# powerblade_3v5.net
KiCad netlist of a schematic drawn in EAGLE
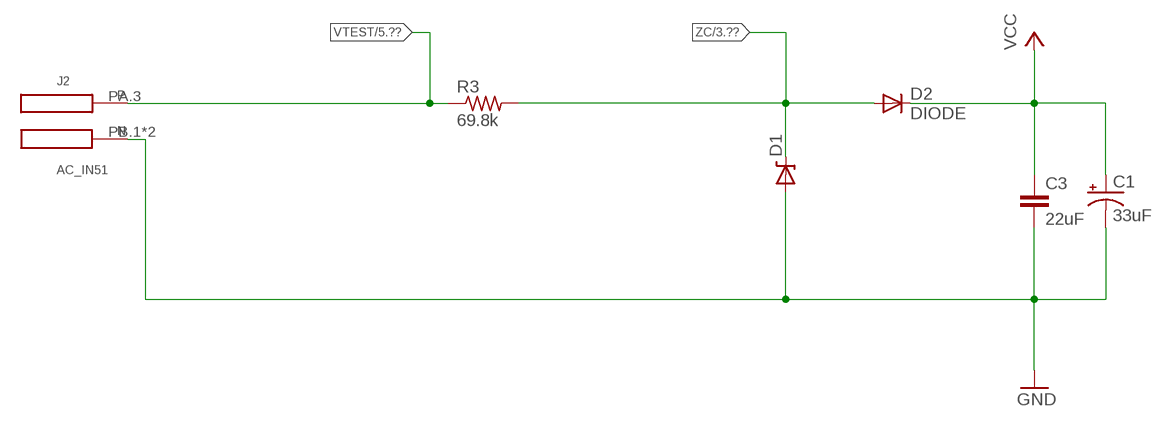
[diagram p0: schematic, sheet 1]
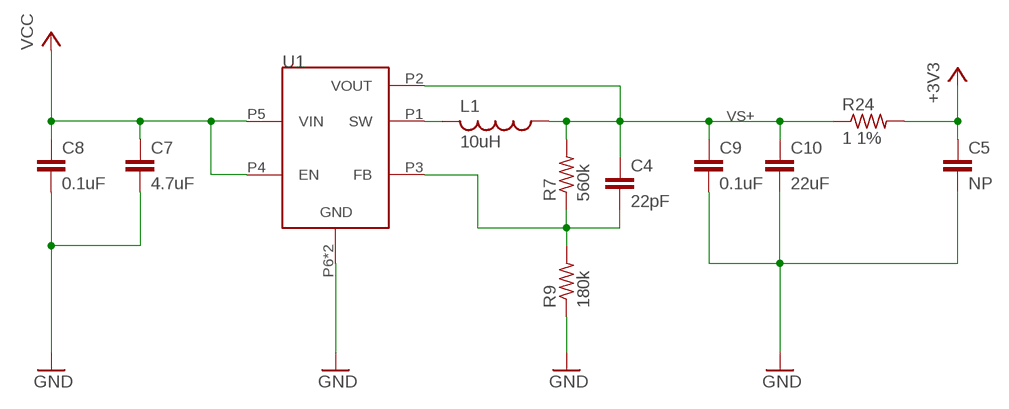
[diagram p1: schematic, sheet 2]
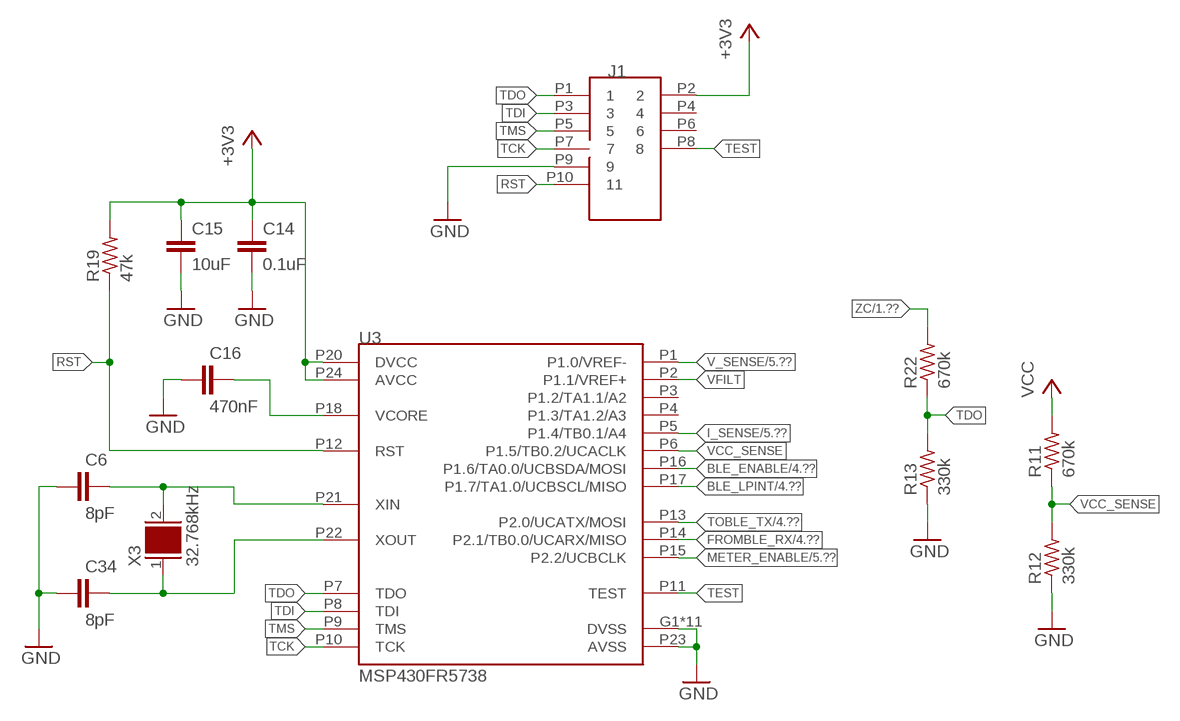
[diagram p2: schematic, sheet 3]
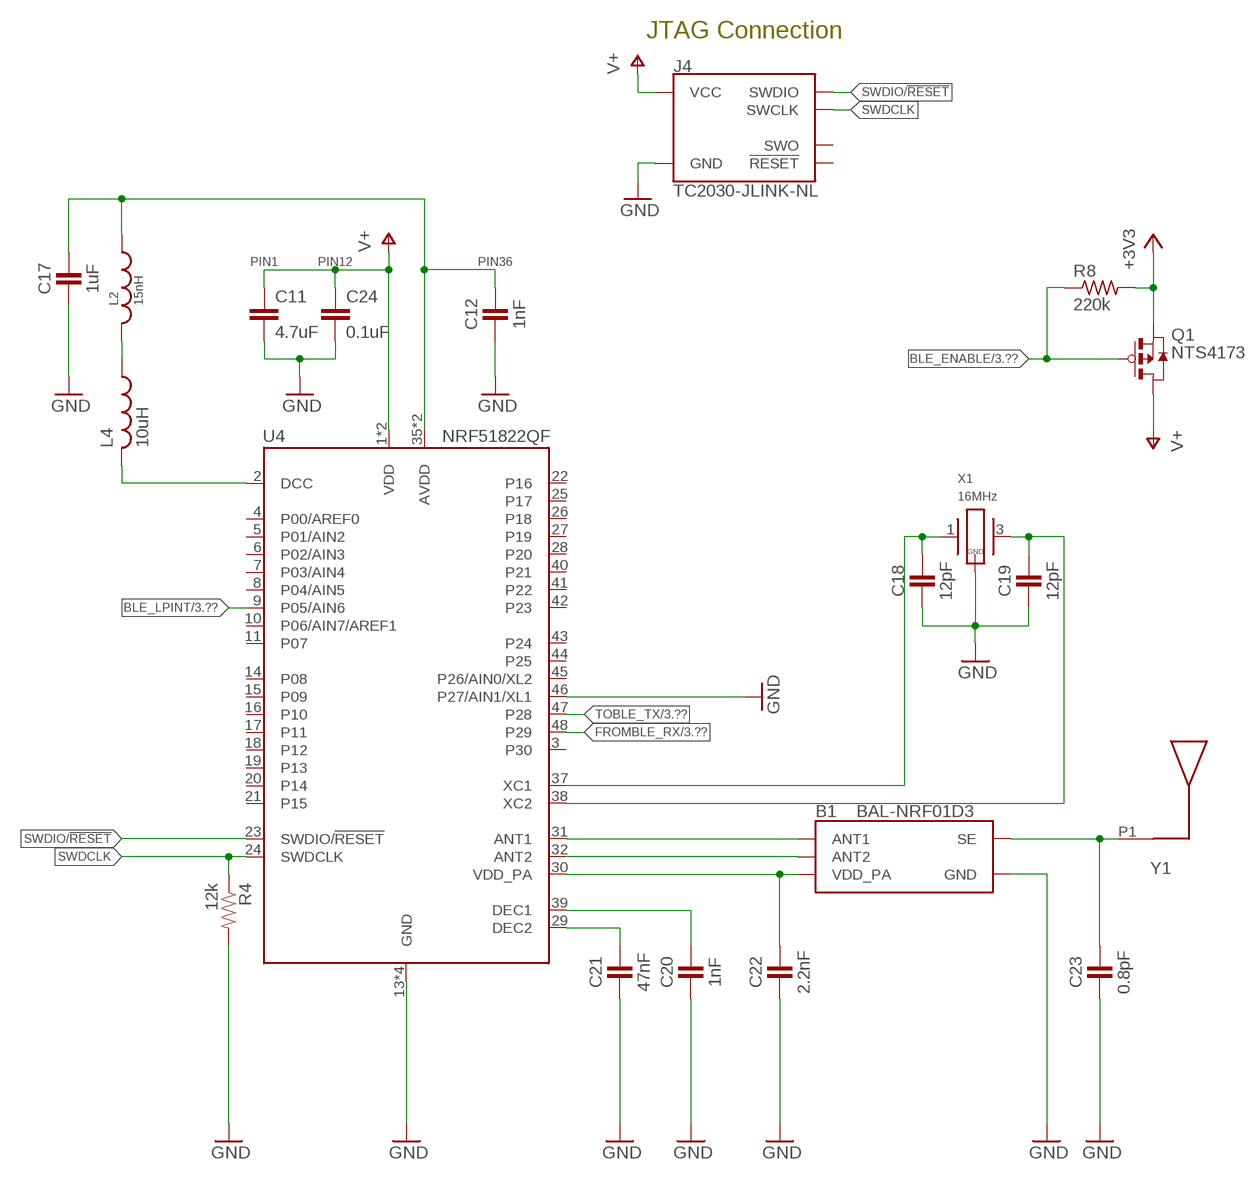
[diagram p3: schematic, sheet 4]
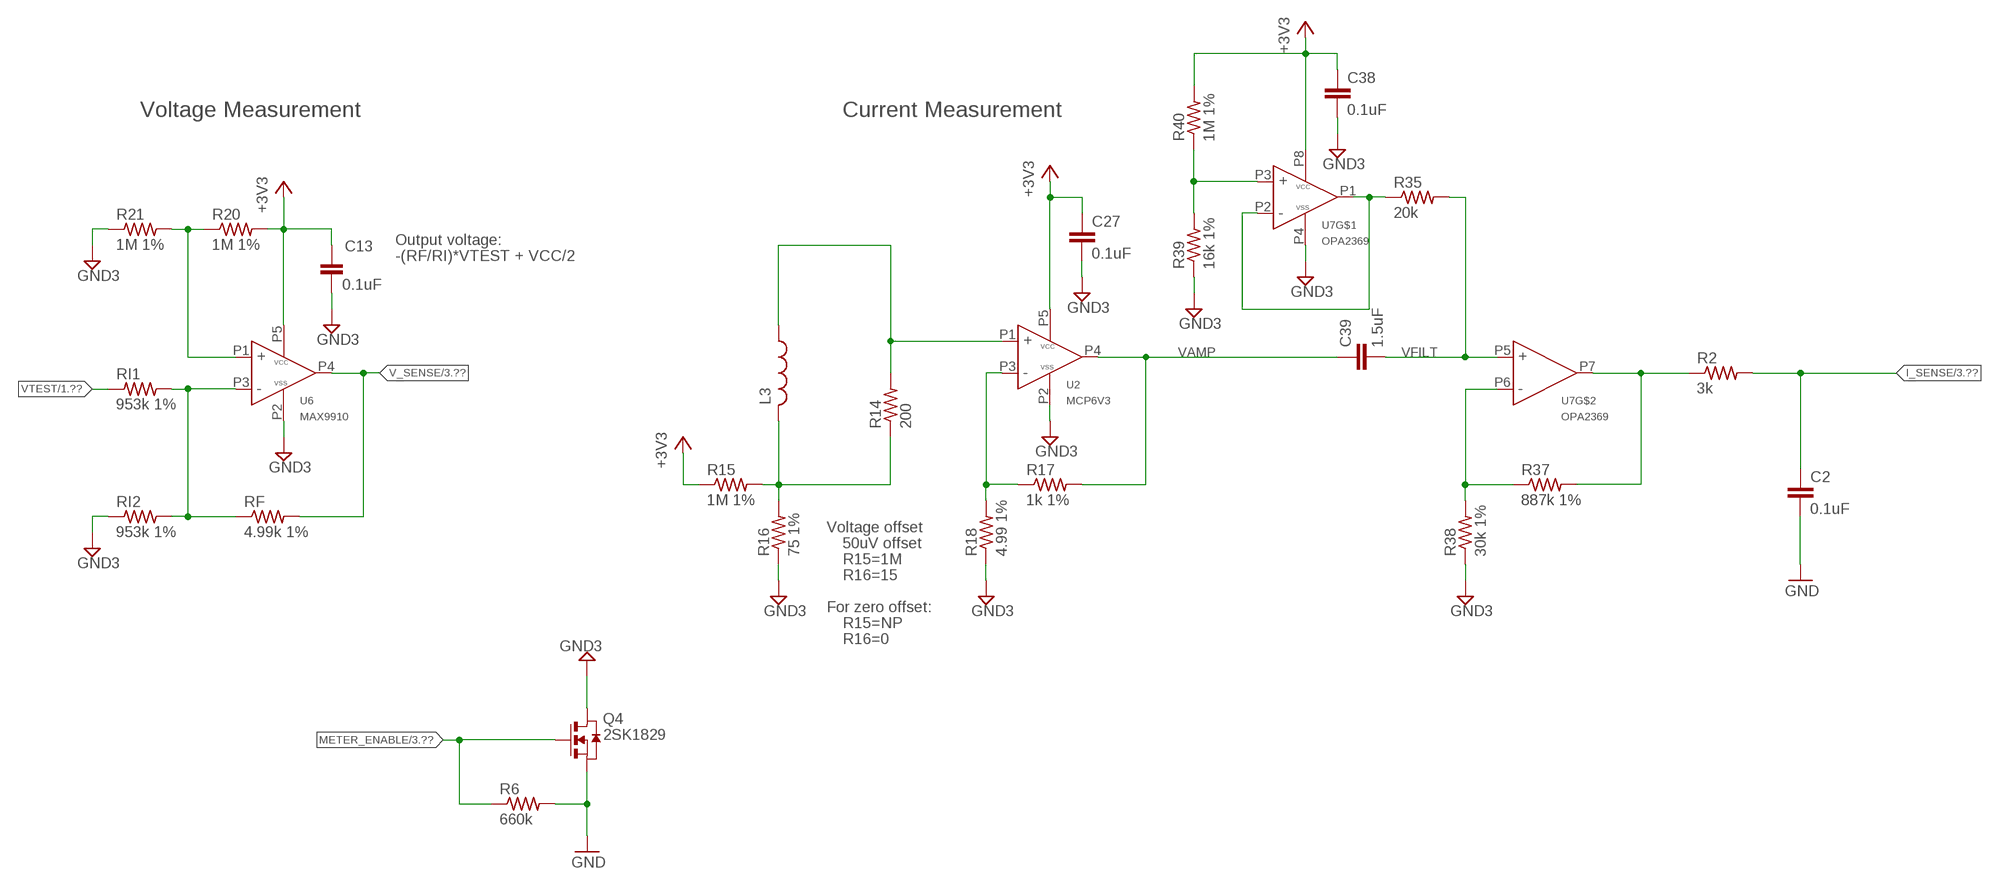
[diagram p4: schematic, sheet 5]

(export (version "E")
  (design (tool "Eeschema 10.0.6"))
  (components
    (comp (ref "B1")
      (value "BAL-NRF01D3")
      (footprint "eagle-import:BAL-NRF01D3")
      (libsource (lib "eagle-import") (part "BAL-NRF01D3"))
    )
    (comp (ref "C11")
      (value "4.7uF")
      (footprint "eagle-import:C0402")
      (libsource (lib "eagle-import") (part "C-EUC0402"))
    )
    (comp (ref "C12")
      (value "1nF")
      (footprint "eagle-import:0402_CAP")
      (libsource (lib "eagle-import") (part "CAPACITOR"))
    )
    (comp (ref "C17")
      (value "1uF")
      (footprint "eagle-import:0402_CAP")
      (libsource (lib "eagle-import") (part "CAPACITOR"))
    )
    (comp (ref "C18")
      (value "12pF")
      (footprint "eagle-import:0402_CAP")
      (libsource (lib "eagle-import") (part "CAPACITOR"))
    )
    (comp (ref "C19")
      (value "12pF")
      (footprint "eagle-import:0402_CAP")
      (libsource (lib "eagle-import") (part "CAPACITOR"))
    )
    (comp (ref "C20")
      (value "1nF")
      (footprint "eagle-import:0402_CAP")
      (libsource (lib "eagle-import") (part "CAPACITOR"))
    )
    (comp (ref "C21")
      (value "47nF")
      (footprint "eagle-import:0402_CAP")
      (libsource (lib "eagle-import") (part "CAPACITOR"))
    )
    (comp (ref "C22")
      (value "2.2nF")
      (footprint "eagle-import:0402_CAP")
      (libsource (lib "eagle-import") (part "CAPACITOR"))
    )
    (comp (ref "C23")
      (value "0.8pF")
      (footprint "eagle-import:0402_CAP")
      (libsource (lib "eagle-import") (part "CAPACITOR"))
    )
    (comp (ref "C24")
      (value "0.1uF")
      (footprint "eagle-import:C0402")
      (libsource (lib "eagle-import") (part "C-EUC0402"))
    )
    (comp (ref "J4")
      (value "TC2030-JLINK-NL")
      (footprint "eagle-import:TC2030-IDC-NL")
      (libsource (lib "eagle-import") (part "TC2030-JLINK-NL"))
    )
    (comp (ref "L2")
      (value "15nH")
      (footprint "eagle-import:0402_CAP")
      (libsource (lib "eagle-import") (part "INDUCTOR0402"))
    )
    (comp (ref "L4")
      (value "10uH")
      (footprint "eagle-import:C0603_TN")
      (libsource (lib "eagle-import") (part "L-USL0603_TN"))
    )
    (comp (ref "Q1")
      (value "NTS4173")
      (footprint "eagle-import:SC-70-3")
      (libsource (lib "eagle-import") (part "NTS4173"))
    )
    (comp (ref "R4")
      (value "12k")
      (footprint "eagle-import:0402_RES")
      (libsource (lib "eagle-import") (part "RESISTOR"))
    )
    (comp (ref "R8")
      (value "220k")
      (footprint "eagle-import:R0402_SM")
      (libsource (lib "eagle-import") (part "R-US_R0402_SM"))
    )
    (comp (ref "U4")
      (value "NRF51822QF")
      (footprint "eagle-import:QFN-48-6MM")
      (libsource (lib "eagle-import") (part "NRF51822QF"))
    )
    (comp (ref "X1")
      (value "16MHz")
      (footprint "eagle-import:TXC-8Y")
      (libsource (lib "eagle-import") (part "TXC-8Y"))
    )
    (comp (ref "Y1")
      (value "UREACH_XTEND")
      (footprint "eagle-import:UREACH_XTEND")
      (libsource (lib "eagle-import") (part "UREACH_XTEND"))
    )
    (comp (ref "C2")
      (value "0.1uF")
      (footprint "eagle-import:C0402")
      (libsource (lib "eagle-import") (part "C-EUC0402"))
    )
    (comp (ref "C13")
      (value "0.1uF")
      (footprint "eagle-import:0402_CAP")
      (libsource (lib "eagle-import") (part "CAPACITOR"))
    )
    (comp (ref "C27")
      (value "0.1uF")
      (footprint "eagle-import:C0402")
      (libsource (lib "eagle-import") (part "C-EUC0402"))
    )
    (comp (ref "C38")
      (value "0.1uF")
      (footprint "eagle-import:C0402")
      (libsource (lib "eagle-import") (part "C-EUC0402"))
    )
    (comp (ref "C39")
      (value "1.5uF")
      (footprint "eagle-import:C0402")
      (libsource (lib "eagle-import") (part "C-EUC0402"))
    )
    (comp (ref "L3")
      (value "L-USL0805")
      (footprint "eagle-import:L0805")
      (libsource (lib "eagle-import") (part "L-USL0805"))
    )
    (comp (ref "Q4")
      (value "2SK1829")
      (footprint "eagle-import:SC-70-3")
      (libsource (lib "eagle-import") (part "2SK1829"))
    )
    (comp (ref "R2")
      (value "3k")
      (footprint "eagle-import:R0402_SM")
      (libsource (lib "eagle-import") (part "R-US_R0402_SM"))
    )
    (comp (ref "R6")
      (value "660k")
      (footprint "eagle-import:R0402")
      (libsource (lib "eagle-import") (part "R-US_R0402"))
    )
    (comp (ref "R14")
      (value "200")
      (footprint "eagle-import:R0402")
      (libsource (lib "eagle-import") (part "R-US_R0402"))
    )
    (comp (ref "R15")
      (value "1M 1%")
      (footprint "eagle-import:R0402")
      (libsource (lib "eagle-import") (part "R-US_R0402"))
    )
    (comp (ref "R16")
      (value "75 1%")
      (footprint "eagle-import:R0402")
      (libsource (lib "eagle-import") (part "R-US_R0402"))
    )
    (comp (ref "R17")
      (value "1k 1%")
      (footprint "eagle-import:R0402")
      (libsource (lib "eagle-import") (part "R-US_R0402"))
    )
    (comp (ref "R18")
      (value "4.99 1%")
      (footprint "eagle-import:R0402")
      (libsource (lib "eagle-import") (part "R-US_R0402"))
    )
    (comp (ref "R20")
      (value "1M 1%")
      (footprint "eagle-import:R0402")
      (libsource (lib "eagle-import") (part "R-US_R0402"))
    )
    (comp (ref "R21")
      (value "1M 1%")
      (footprint "eagle-import:R0402_SM")
      (libsource (lib "eagle-import") (part "R-US_R0402_SM"))
    )
    (comp (ref "R35")
      (value "20k")
      (footprint "eagle-import:R0402")
      (libsource (lib "eagle-import") (part "R-US_R0402"))
    )
    (comp (ref "R37")
      (value "887k 1%")
      (footprint "eagle-import:R0402")
      (libsource (lib "eagle-import") (part "R-US_R0402"))
    )
    (comp (ref "R38")
      (value "30k 1%")
      (footprint "eagle-import:R0402")
      (libsource (lib "eagle-import") (part "R-US_R0402"))
    )
    (comp (ref "R39")
      (value "16k 1%")
      (footprint "eagle-import:R0402")
      (libsource (lib "eagle-import") (part "R-US_R0402"))
    )
    (comp (ref "R40")
      (value "1M 1%")
      (footprint "eagle-import:R0402")
      (libsource (lib "eagle-import") (part "R-US_R0402"))
    )
    (comp (ref "RF")
      (value "4.99k 1%")
      (footprint "eagle-import:R0402")
      (libsource (lib "eagle-import") (part "R-US_R0402"))
    )
    (comp (ref "RI1")
      (value "953k 1%")
      (footprint "eagle-import:R0402")
      (libsource (lib "eagle-import") (part "R-US_R0402"))
    )
    (comp (ref "RI2")
      (value "953k 1%")
      (footprint "eagle-import:R0402")
      (libsource (lib "eagle-import") (part "R-US_R0402"))
    )
    (comp (ref "U2")
      (value "MCP6V3")
      (footprint "eagle-import:SC70-5")
      (fields (field (name "DIGIKEY") "296-19547-1-ND"))
      (libsource (lib "eagle-import") (part "MCP6V3"))
    )
    (comp (ref "U6")
      (value "MAX9910")
      (footprint "eagle-import:SC70-5")
      (fields (field (name "DIGIKEY") "296-25252-1-ND"))
      (libsource (lib "eagle-import") (part "MAX9910"))
    )
    (comp (ref "U7")
      (value "OPA2369")
      (footprint "eagle-import:SOT-23-8")
      (libsource (lib "eagle-import") (part "OPA2369"))
    )
    (comp (ref "C6")
      (value "8pF")
      (footprint "eagle-import:C0402")
      (libsource (lib "eagle-import") (part "C-EUC0402"))
    )
    (comp (ref "C14")
      (value "0.1uF")
      (footprint "eagle-import:C0402")
      (libsource (lib "eagle-import") (part "C-EUC0402"))
    )
    (comp (ref "C15")
      (value "10uF")
      (footprint "eagle-import:C0603_SM")
      (libsource (lib "eagle-import") (part "C-EUC0603_SM"))
    )
    (comp (ref "C16")
      (value "470nF")
      (footprint "eagle-import:C0402")
      (libsource (lib "eagle-import") (part "C-EUC0402"))
    )
    (comp (ref "C34")
      (value "8pF")
      (footprint "eagle-import:C0402")
      (libsource (lib "eagle-import") (part "C-EUC0402"))
    )
    (comp (ref "J1")
      (value "JTAG_14PIN_IDC-ND")
      (footprint "eagle-import:TC2050-IDC-NL-430-ND")
      (libsource (lib "eagle-import") (part "JTAG_14PIN_IDC-ND"))
    )
    (comp (ref "R11")
      (value "670k")
      (footprint "eagle-import:R0402")
      (libsource (lib "eagle-import") (part "R-US_R0402"))
    )
    (comp (ref "R12")
      (value "330k")
      (footprint "eagle-import:R0402")
      (libsource (lib "eagle-import") (part "R-US_R0402"))
    )
    (comp (ref "R13")
      (value "330k")
      (footprint "eagle-import:R0402")
      (libsource (lib "eagle-import") (part "R-US_R0402"))
    )
    (comp (ref "R19")
      (value "47k")
      (footprint "eagle-import:R0402")
      (libsource (lib "eagle-import") (part "R-US_R0402"))
    )
    (comp (ref "R22")
      (value "670k")
      (footprint "eagle-import:R0402")
      (libsource (lib "eagle-import") (part "R-US_R0402"))
    )
    (comp (ref "U3")
      (value "MSP430FR5738")
      (footprint "eagle-import:VQFN-24")
      (libsource (lib "eagle-import") (part "MSP430FR5738"))
    )
    (comp (ref "X3")
      (value "32.768kHz")
      (footprint "eagle-import:0805")
      (libsource (lib "eagle-import") (part "CRYSTAL_0805"))
    )
    (comp (ref "C1")
      (value "33uF")
      (footprint "eagle-import:CPOL0805_SM")
      (libsource (lib "eagle-import") (part "CPOL-US0805_SM"))
    )
    (comp (ref "C3")
      (value "22uF")
      (footprint "eagle-import:C0603_SM")
      (libsource (lib "eagle-import") (part "C-EUC0603_SM"))
    )
    (comp (ref "D1")
      (value "ZENERBZT52")
      (footprint "eagle-import:BZT52")
      (fields (field (name "DIGIKEY") "BZT52C10T-7DICT-ND "))
      (libsource (lib "eagle-import") (part "ZENERBZT52"))
    )
    (comp (ref "D2")
      (value "DIODE")
      (footprint "eagle-import:BAS521")
      (libsource (lib "eagle-import") (part "DIODE"))
    )
    (comp (ref "J2")
      (value "AC_IN51")
      (footprint "eagle-import:AC3_51")
      (libsource (lib "eagle-import") (part "AC_IN51"))
    )
    (comp (ref "R3")
      (value "69.8k")
      (footprint "eagle-import:R1210")
      (libsource (lib "eagle-import") (part "R-US_R1210"))
    )
    (comp (ref "C4")
      (value "22pF")
      (footprint "eagle-import:C0402")
      (libsource (lib "eagle-import") (part "C-EUC0402"))
    )
    (comp (ref "C5")
      (value "NP")
      (footprint "eagle-import:C0603_TN")
      (libsource (lib "eagle-import") (part "C-EUC0603_TN"))
    )
    (comp (ref "C7")
      (value "4.7uF")
      (footprint "eagle-import:C0402")
      (libsource (lib "eagle-import") (part "C-EUC0402"))
    )
    (comp (ref "C8")
      (value "0.1uF")
      (footprint "eagle-import:C0402")
      (libsource (lib "eagle-import") (part "C-EUC0402"))
    )
    (comp (ref "C9")
      (value "0.1uF")
      (footprint "eagle-import:C0402_SM")
      (libsource (lib "eagle-import") (part "C-EUC0402_SM"))
    )
    (comp (ref "C10")
      (value "22uF")
      (footprint "eagle-import:C0603_SM")
      (libsource (lib "eagle-import") (part "C-EUC0603_SM"))
    )
    (comp (ref "L1")
      (value "10uH")
      (footprint "eagle-import:L0805")
      (libsource (lib "eagle-import") (part "L-USL0805"))
    )
    (comp (ref "R7")
      (value "560k")
      (footprint "eagle-import:R0402")
      (libsource (lib "eagle-import") (part "R-US_R0402"))
    )
    (comp (ref "R9")
      (value "180k")
      (footprint "eagle-import:R0402")
      (libsource (lib "eagle-import") (part "R-US_R0402"))
    )
    (comp (ref "R24")
      (value "1 1%")
      (footprint "eagle-import:R0603_SM")
      (libsource (lib "eagle-import") (part "R-US_R0603_SM"))
    )
    (comp (ref "U1")
      (value "TPS62122")
      (footprint "eagle-import:WDFN-6")
      (libsource (lib "eagle-import") (part "TPS62122"))
    )
  )
  (nets
    (net (code "1") (name "+3V3") (class "Default")
      (node (ref "C13") (pin "1") (pinfunction "1_1") (pintype "bidirectional"))
      (node (ref "C14") (pin "1") (pinfunction "1_1") (pintype "passive"))
      (node (ref "C15") (pin "1") (pinfunction "1_1") (pintype "passive"))
      (node (ref "C27") (pin "1") (pinfunction "1_1") (pintype "passive"))
      (node (ref "C38") (pin "1") (pinfunction "1_1") (pintype "passive"))
      (node (ref "C5") (pin "1") (pinfunction "1_1") (pintype "passive"))
      (node (ref "J1") (pin "P2") (pinfunction "2_P2") (pintype "bidirectional"))
      (node (ref "Q1") (pin "P2") (pinfunction "S_P2") (pintype "passive"))
      (node (ref "R15") (pin "1") (pinfunction "1_1") (pintype "passive"))
      (node (ref "R19") (pin "2") (pinfunction "2_2") (pintype "passive"))
      (node (ref "R20") (pin "2") (pinfunction "2_2") (pintype "passive"))
      (node (ref "R24") (pin "2") (pinfunction "2_2") (pintype "passive"))
      (node (ref "R40") (pin "2") (pinfunction "2_2") (pintype "passive"))
      (node (ref "R8") (pin "2") (pinfunction "2_2") (pintype "passive"))
      (node (ref "U2") (pin "P5") (pinfunction "VCC_P5") (pintype "bidirectional"))
      (node (ref "U3") (pin "P20") (pinfunction "DVCC_P20") (pintype "bidirectional"))
      (node (ref "U3") (pin "P24") (pinfunction "AVCC_P24") (pintype "bidirectional"))
      (node (ref "U6") (pin "P5") (pinfunction "VCC_P5") (pintype "bidirectional"))
      (node (ref "U7") (pin "P8") (pinfunction "VCC_P8") (pintype "bidirectional"))
    )
    (net (code "2") (name "BLE_ENABLE") (class "Default")
      (node (ref "Q1") (pin "P1") (pinfunction "G_P1") (pintype "passive"))
      (node (ref "R8") (pin "1") (pinfunction "1_1") (pintype "passive"))
      (node (ref "U3") (pin "P16") (pinfunction "P1.6/TA0.0/UCBSDA/MOSI_P16") (pintype "bidirectional"))
    )
    (net (code "3") (name "BLE_LPINT") (class "Default")
      (node (ref "U3") (pin "P17") (pinfunction "P1.7/TA1.0/UCBSCL/MISO_P17") (pintype "bidirectional"))
      (node (ref "U4") (pin "9") (pinfunction "P05/AIN6_9") (pintype "bidirectional"))
    )
    (net (code "4") (name "FROMBLE_RX") (class "Default")
      (node (ref "U3") (pin "P14") (pinfunction "P2.1/TB0.0/UCARX/MISO_P14") (pintype "bidirectional"))
      (node (ref "U4") (pin "48") (pinfunction "P29_48") (pintype "bidirectional"))
    )
    (net (code "5") (name "GND") (class "Default")
      (node (ref "B1") (pin "GND") (pinfunction "GND_GND") (pintype "bidirectional"))
      (node (ref "C1") (pin "-") (pinfunction "-_-") (pintype "passive"))
      (node (ref "C10") (pin "2") (pinfunction "2_2") (pintype "passive"))
      (node (ref "C11") (pin "2") (pinfunction "2_2") (pintype "passive"))
      (node (ref "C12") (pin "2") (pinfunction "2_2") (pintype "bidirectional"))
      (node (ref "C14") (pin "2") (pinfunction "2_2") (pintype "passive"))
      (node (ref "C15") (pin "2") (pinfunction "2_2") (pintype "passive"))
      (node (ref "C16") (pin "1") (pinfunction "1_1") (pintype "passive"))
      (node (ref "C17") (pin "2") (pinfunction "2_2") (pintype "bidirectional"))
      (node (ref "C18") (pin "2") (pinfunction "2_2") (pintype "bidirectional"))
      (node (ref "C19") (pin "2") (pinfunction "2_2") (pintype "bidirectional"))
      (node (ref "C2") (pin "2") (pinfunction "2_2") (pintype "passive"))
      (node (ref "C20") (pin "2") (pinfunction "2_2") (pintype "bidirectional"))
      (node (ref "C21") (pin "2") (pinfunction "2_2") (pintype "bidirectional"))
      (node (ref "C22") (pin "2") (pinfunction "2_2") (pintype "bidirectional"))
      (node (ref "C23") (pin "2") (pinfunction "2_2") (pintype "bidirectional"))
      (node (ref "C24") (pin "2") (pinfunction "2_2") (pintype "passive"))
      (node (ref "C3") (pin "2") (pinfunction "2_2") (pintype "passive"))
      (node (ref "C34") (pin "1") (pinfunction "1_1") (pintype "passive"))
      (node (ref "C5") (pin "2") (pinfunction "2_2") (pintype "passive"))
      (node (ref "C6") (pin "1") (pinfunction "1_1") (pintype "passive"))
      (node (ref "C7") (pin "2") (pinfunction "2_2") (pintype "passive"))
      (node (ref "C8") (pin "2") (pinfunction "2_2") (pintype "passive"))
      (node (ref "C9") (pin "2") (pinfunction "2_2") (pintype "passive"))
      (node (ref "D1") (pin "A") (pinfunction "A_A") (pintype "passive"))
      (node (ref "J1") (pin "P9") (pinfunction "9_P9") (pintype "bidirectional"))
      (node (ref "J2") (pin "PB.1") (pinfunction "N_PB.1") (pintype "bidirectional"))
      (node (ref "J2") (pin "PB.3") (pinfunction "N_PB.3") (pintype "bidirectional"))
      (node (ref "J4") (pin "5") (pinfunction "GND_5") (pintype "bidirectional"))
      (node (ref "Q4") (pin "P2") (pinfunction "S_P2") (pintype "passive"))
      (node (ref "R12") (pin "1") (pinfunction "1_1") (pintype "passive"))
      (node (ref "R13") (pin "1") (pinfunction "1_1") (pintype "passive"))
      (node (ref "R4") (pin "2") (pinfunction "2_2") (pintype "passive"))
      (node (ref "R6") (pin "2") (pinfunction "2_2") (pintype "passive"))
      (node (ref "R9") (pin "1") (pinfunction "1_1") (pintype "passive"))
      (node (ref "U1") (pin "P6") (pinfunction "GND_P6") (pintype "bidirectional"))
      (node (ref "U1") (pin "PAD") (pinfunction "GND_PAD") (pintype "bidirectional"))
      (node (ref "U3") (pin "G1") (pinfunction "DVSS_G1") (pintype "bidirectional"))
      (node (ref "U3") (pin "G2") (pinfunction "DVSS_G2") (pintype "bidirectional"))
      (node (ref "U3") (pin "G3") (pinfunction "DVSS_G3") (pintype "bidirectional"))
      (node (ref "U3") (pin "G4") (pinfunction "DVSS_G4") (pintype "bidirectional"))
      (node (ref "U3") (pin "G5") (pinfunction "DVSS_G5") (pintype "bidirectional"))
      (node (ref "U3") (pin "G6") (pinfunction "DVSS_G6") (pintype "bidirectional"))
      (node (ref "U3") (pin "G7") (pinfunction "DVSS_G7") (pintype "bidirectional"))
      (node (ref "U3") (pin "G8") (pinfunction "DVSS_G8") (pintype "bidirectional"))
      (node (ref "U3") (pin "G9") (pinfunction "DVSS_G9") (pintype "bidirectional"))
      (node (ref "U3") (pin "P19") (pinfunction "DVSS_P19") (pintype "bidirectional"))
      (node (ref "U3") (pin "P23") (pinfunction "AVSS_P23") (pintype "bidirectional"))
      (node (ref "U3") (pin "PAD") (pinfunction "DVSS_PAD") (pintype "bidirectional"))
      (node (ref "U4") (pin "13") (pinfunction "GND_13") (pintype "bidirectional"))
      (node (ref "U4") (pin "33") (pinfunction "GND_33") (pintype "bidirectional"))
      (node (ref "U4") (pin "34") (pinfunction "GND_34") (pintype "bidirectional"))
      (node (ref "U4") (pin "46") (pinfunction "P27/AIN1/XL1_46") (pintype "bidirectional"))
      (node (ref "U4") (pin "GND") (pinfunction "GND_GND") (pintype "bidirectional"))
      (node (ref "X1") (pin "2") (pinfunction "GND_2") (pintype "bidirectional"))
      (node (ref "X1") (pin "4") (pinfunction "GND_4") (pintype "bidirectional"))
    )
    (net (code "6") (name "GND3") (class "Default")
      (node (ref "C13") (pin "2") (pinfunction "2_2") (pintype "bidirectional"))
      (node (ref "C27") (pin "2") (pinfunction "2_2") (pintype "passive"))
      (node (ref "C38") (pin "2") (pinfunction "2_2") (pintype "passive"))
      (node (ref "Q4") (pin "P3") (pinfunction "D_P3") (pintype "passive"))
      (node (ref "R16") (pin "1") (pinfunction "1_1") (pintype "passive"))
      (node (ref "R18") (pin "1") (pinfunction "1_1") (pintype "passive"))
      (node (ref "R21") (pin "1") (pinfunction "1_1") (pintype "passive"))
      (node (ref "R38") (pin "1") (pinfunction "1_1") (pintype "passive"))
      (node (ref "R39") (pin "1") (pinfunction "1_1") (pintype "passive"))
      (node (ref "RI2") (pin "1") (pinfunction "1_1") (pintype "passive"))
      (node (ref "U2") (pin "P2") (pinfunction "VSS_P2") (pintype "bidirectional"))
      (node (ref "U6") (pin "P2") (pinfunction "VSS_P2") (pintype "bidirectional"))
      (node (ref "U7") (pin "P4") (pinfunction "VSS_P4") (pintype "bidirectional"))
    )
    (net (code "7") (name "I_SENSE") (class "Default")
      (node (ref "C2") (pin "1") (pinfunction "1_1") (pintype "passive"))
      (node (ref "R2") (pin "2") (pinfunction "2_2") (pintype "passive"))
      (node (ref "U3") (pin "P5") (pinfunction "P1.4/TB0.1/A4_P5") (pintype "bidirectional"))
    )
    (net (code "8") (name "METER_ENABLE") (class "Default")
      (node (ref "Q4") (pin "P1") (pinfunction "G_P1") (pintype "passive"))
      (node (ref "R6") (pin "1") (pinfunction "1_1") (pintype "passive"))
      (node (ref "U3") (pin "P15") (pinfunction "P2.2/UCBCLK_P15") (pintype "bidirectional"))
    )
    (net (code "9") (name "Net-(B1-PadSE)") (class "Default")
      (node (ref "B1") (pin "SE") (pinfunction "SE_SE") (pintype "bidirectional"))
      (node (ref "C23") (pin "1") (pinfunction "1_1") (pintype "bidirectional"))
      (node (ref "Y1") (pin "P1") (pinfunction "P1_P1") (pintype "bidirectional"))
    )
    (net (code "10") (name "Net-(B1-VDD_PA)") (class "Default")
      (node (ref "B1") (pin "VCC") (pinfunction "VDD_PA_VCC") (pintype "bidirectional"))
      (node (ref "C22") (pin "1") (pinfunction "1_1") (pintype "bidirectional"))
      (node (ref "U4") (pin "30") (pinfunction "VDD_PA_30") (pintype "bidirectional"))
    )
    (net (code "11") (name "Net-(C12-Pad1)") (class "Default")
      (node (ref "C12") (pin "1") (pinfunction "1_1") (pintype "bidirectional"))
      (node (ref "C17") (pin "1") (pinfunction "1_1") (pintype "bidirectional"))
      (node (ref "L2") (pin "1") (pinfunction "1_1") (pintype "bidirectional"))
      (node (ref "U4") (pin "35") (pinfunction "AVDD_35") (pintype "bidirectional"))
      (node (ref "U4") (pin "36") (pinfunction "AVDD_36") (pintype "bidirectional"))
    )
    (net (code "12") (name "Net-(L2-Pad2)") (class "Default")
      (node (ref "L2") (pin "2") (pinfunction "2_2") (pintype "bidirectional"))
      (node (ref "L4") (pin "1") (pinfunction "1_1") (pintype "passive"))
    )
    (net (code "13") (name "Net-(L3-Pad2)") (class "Default")
      (node (ref "L3") (pin "2") (pinfunction "2_2") (pintype "passive"))
      (node (ref "R14") (pin "1") (pinfunction "1_1") (pintype "passive"))
      (node (ref "R15") (pin "2") (pinfunction "2_2") (pintype "passive"))
      (node (ref "R16") (pin "2") (pinfunction "2_2") (pintype "passive"))
    )
    (net (code "14") (name "Net-(U1-FB)") (class "Default")
      (node (ref "C4") (pin "2") (pinfunction "2_2") (pintype "passive"))
      (node (ref "R7") (pin "1") (pinfunction "1_1") (pintype "passive"))
      (node (ref "R9") (pin "2") (pinfunction "2_2") (pintype "passive"))
      (node (ref "U1") (pin "P3") (pinfunction "FB_P3") (pintype "bidirectional"))
    )
    (net (code "15") (name "Net-(U1-SW)") (class "Default")
      (node (ref "L1") (pin "2") (pinfunction "2_2") (pintype "passive"))
      (node (ref "U1") (pin "P1") (pinfunction "SW_P1") (pintype "bidirectional"))
    )
    (net (code "16") (name "Net-(U2-IN+)") (class "Default")
      (node (ref "L3") (pin "1") (pinfunction "1_1") (pintype "passive"))
      (node (ref "R14") (pin "2") (pinfunction "2_2") (pintype "passive"))
      (node (ref "U2") (pin "P1") (pinfunction "IN+_P1") (pintype "bidirectional"))
    )
    (net (code "17") (name "Net-(U2-IN-)") (class "Default")
      (node (ref "R17") (pin "1") (pinfunction "1_1") (pintype "passive"))
      (node (ref "R18") (pin "2") (pinfunction "2_2") (pintype "passive"))
      (node (ref "U2") (pin "P3") (pinfunction "IN-_P3") (pintype "bidirectional"))
    )
    (net (code "18") (name "Net-(U3-VCORE)") (class "Default")
      (node (ref "C16") (pin "2") (pinfunction "2_2") (pintype "passive"))
      (node (ref "U3") (pin "P18") (pinfunction "VCORE_P18") (pintype "bidirectional"))
    )
    (net (code "19") (name "Net-(U3-XIN)") (class "Default")
      (node (ref "C6") (pin "2") (pinfunction "2_2") (pintype "passive"))
      (node (ref "U3") (pin "P21") (pinfunction "XIN_P21") (pintype "bidirectional"))
      (node (ref "X3") (pin "2") (pinfunction "P2_2") (pintype "bidirectional"))
    )
    (net (code "20") (name "Net-(U3-XOUT)") (class "Default")
      (node (ref "C34") (pin "2") (pinfunction "2_2") (pintype "passive"))
      (node (ref "U3") (pin "P22") (pinfunction "XOUT_P22") (pintype "bidirectional"))
      (node (ref "X3") (pin "1") (pinfunction "P1_1") (pintype "bidirectional"))
    )
    (net (code "21") (name "Net-(U4-ANT1)") (class "Default")
      (node (ref "B1") (pin "ANT1") (pinfunction "ANT1_ANT1") (pintype "bidirectional"))
      (node (ref "U4") (pin "31") (pinfunction "ANT1_31") (pintype "bidirectional"))
    )
    (net (code "22") (name "Net-(U4-ANT2)") (class "Default")
      (node (ref "B1") (pin "ANT2") (pinfunction "ANT2_ANT2") (pintype "bidirectional"))
      (node (ref "U4") (pin "32") (pinfunction "ANT2_32") (pintype "bidirectional"))
    )
    (net (code "23") (name "Net-(U4-DCC)") (class "Default")
      (node (ref "L4") (pin "2") (pinfunction "2_2") (pintype "passive"))
      (node (ref "U4") (pin "2") (pinfunction "DCC_2") (pintype "bidirectional"))
    )
    (net (code "24") (name "Net-(U4-DEC1)") (class "Default")
      (node (ref "C20") (pin "1") (pinfunction "1_1") (pintype "bidirectional"))
      (node (ref "U4") (pin "39") (pinfunction "DEC1_39") (pintype "bidirectional"))
    )
    (net (code "25") (name "Net-(U4-DEC2)") (class "Default")
      (node (ref "C21") (pin "1") (pinfunction "1_1") (pintype "bidirectional"))
      (node (ref "U4") (pin "29") (pinfunction "DEC2_29") (pintype "bidirectional"))
    )
    (net (code "26") (name "Net-(U4-XC1)") (class "Default")
      (node (ref "C18") (pin "1") (pinfunction "1_1") (pintype "bidirectional"))
      (node (ref "U4") (pin "37") (pinfunction "XC1_37") (pintype "bidirectional"))
      (node (ref "X1") (pin "1") (pinfunction "1_1") (pintype "bidirectional"))
    )
    (net (code "27") (name "Net-(U4-XC2)") (class "Default")
      (node (ref "C19") (pin "1") (pinfunction "1_1") (pintype "bidirectional"))
      (node (ref "U4") (pin "38") (pinfunction "XC2_38") (pintype "bidirectional"))
      (node (ref "X1") (pin "3") (pinfunction "2_3") (pintype "bidirectional"))
    )
    (net (code "28") (name "Net-(U6-IN+)") (class "Default")
      (node (ref "R20") (pin "1") (pinfunction "1_1") (pintype "passive"))
      (node (ref "R21") (pin "2") (pinfunction "2_2") (pintype "passive"))
      (node (ref "U6") (pin "P1") (pinfunction "IN+_P1") (pintype "bidirectional"))
    )
    (net (code "29") (name "Net-(U6-IN-)") (class "Default")
      (node (ref "RF") (pin "1") (pinfunction "1_1") (pintype "passive"))
      (node (ref "RI1") (pin "2") (pinfunction "2_2") (pintype "passive"))
      (node (ref "RI2") (pin "2") (pinfunction "2_2") (pintype "passive"))
      (node (ref "U6") (pin "P3") (pinfunction "IN-_P3") (pintype "bidirectional"))
    )
    (net (code "30") (name "Net-(U7A-IN+)") (class "Default")
      (node (ref "R39") (pin "2") (pinfunction "2_2") (pintype "passive"))
      (node (ref "R40") (pin "1") (pinfunction "1_1") (pintype "passive"))
      (node (ref "U7") (pin "P3") (pinfunction "IN+_P3") (pintype "bidirectional"))
    )
    (net (code "31") (name "Net-(U7A-IN-)") (class "Default")
      (node (ref "R35") (pin "1") (pinfunction "1_1") (pintype "passive"))
      (node (ref "U7") (pin "P1") (pinfunction "OUT_P1") (pintype "bidirectional"))
      (node (ref "U7") (pin "P2") (pinfunction "IN-_P2") (pintype "bidirectional"))
    )
    (net (code "32") (name "Net-(U7B-IN-)") (class "Default")
      (node (ref "R37") (pin "1") (pinfunction "1_1") (pintype "passive"))
      (node (ref "R38") (pin "2") (pinfunction "2_2") (pintype "passive"))
      (node (ref "U7") (pin "P6") (pinfunction "IN-_P6") (pintype "bidirectional"))
    )
    (net (code "33") (name "Net-(U7B-OUT)") (class "Default")
      (node (ref "R2") (pin "1") (pinfunction "1_1") (pintype "passive"))
      (node (ref "R37") (pin "2") (pinfunction "2_2") (pintype "passive"))
      (node (ref "U7") (pin "P7") (pinfunction "OUT_P7") (pintype "bidirectional"))
    )
    (net (code "34") (name "RST") (class "Default")
      (node (ref "J1") (pin "P10") (pinfunction "11_P10") (pintype "bidirectional"))
      (node (ref "R19") (pin "1") (pinfunction "1_1") (pintype "passive"))
      (node (ref "U3") (pin "P12") (pinfunction "RST_P12") (pintype "bidirectional"))
    )
    (net (code "35") (name "SWDCLK") (class "Default")
      (node (ref "J4") (pin "4") (pinfunction "SWCLK_4") (pintype "bidirectional"))
      (node (ref "R4") (pin "1") (pinfunction "1_1") (pintype "passive"))
      (node (ref "U4") (pin "24") (pinfunction "SWDCLK_24") (pintype "bidirectional"))
    )
    (net (code "36") (name "SWDIO{slash}~{RESET}") (class "Default")
      (node (ref "J4") (pin "2") (pinfunction "SWDIO_2") (pintype "bidirectional"))
      (node (ref "U4") (pin "23") (pinfunction "SWDIO/~{RESET}_23") (pintype "bidirectional"))
    )
    (net (code "37") (name "TCK") (class "Default")
      (node (ref "J1") (pin "P7") (pinfunction "7_P7") (pintype "bidirectional"))
      (node (ref "U3") (pin "P10") (pinfunction "TCK_P10") (pintype "bidirectional"))
    )
    (net (code "38") (name "TDI") (class "Default")
      (node (ref "J1") (pin "P3") (pinfunction "3_P3") (pintype "bidirectional"))
      (node (ref "U3") (pin "P8") (pinfunction "TDI_P8") (pintype "bidirectional"))
    )
    (net (code "39") (name "TDO") (class "Default")
      (node (ref "J1") (pin "P1") (pinfunction "1_P1") (pintype "bidirectional"))
      (node (ref "R13") (pin "2") (pinfunction "2_2") (pintype "passive"))
      (node (ref "R22") (pin "1") (pinfunction "1_1") (pintype "passive"))
      (node (ref "U3") (pin "P7") (pinfunction "TDO_P7") (pintype "bidirectional"))
    )
    (net (code "40") (name "TEST") (class "Default")
      (node (ref "J1") (pin "P8") (pinfunction "8_P8") (pintype "bidirectional"))
      (node (ref "U3") (pin "P11") (pinfunction "TEST_P11") (pintype "bidirectional"))
    )
    (net (code "41") (name "TMS") (class "Default")
      (node (ref "J1") (pin "P5") (pinfunction "5_P5") (pintype "bidirectional"))
      (node (ref "U3") (pin "P9") (pinfunction "TMS_P9") (pintype "bidirectional"))
    )
    (net (code "42") (name "TOBLE_TX") (class "Default")
      (node (ref "U3") (pin "P13") (pinfunction "P2.0/UCATX/MOSI_P13") (pintype "bidirectional"))
      (node (ref "U4") (pin "47") (pinfunction "P28_47") (pintype "bidirectional"))
    )
    (net (code "43") (name "V+") (class "Default")
      (node (ref "C11") (pin "1") (pinfunction "1_1") (pintype "passive"))
      (node (ref "C24") (pin "1") (pinfunction "1_1") (pintype "passive"))
      (node (ref "J4") (pin "1") (pinfunction "VCC_1") (pintype "bidirectional"))
      (node (ref "Q1") (pin "P3") (pinfunction "D_P3") (pintype "passive"))
      (node (ref "U4") (pin "1") (pinfunction "VDD_1") (pintype "bidirectional"))
      (node (ref "U4") (pin "12") (pinfunction "VDD_12") (pintype "bidirectional"))
    )
    (net (code "44") (name "VAMP") (class "Default")
      (node (ref "C39") (pin "1") (pinfunction "1_1") (pintype "passive"))
      (node (ref "R17") (pin "2") (pinfunction "2_2") (pintype "passive"))
      (node (ref "U2") (pin "P4") (pinfunction "OUT_P4") (pintype "bidirectional"))
    )
    (net (code "45") (name "VCC") (class "Default")
      (node (ref "C1") (pin "+") (pinfunction "+_+") (pintype "passive"))
      (node (ref "C3") (pin "1") (pinfunction "1_1") (pintype "passive"))
      (node (ref "C7") (pin "1") (pinfunction "1_1") (pintype "passive"))
      (node (ref "C8") (pin "1") (pinfunction "1_1") (pintype "passive"))
      (node (ref "D2") (pin "C") (pinfunction "C_C") (pintype "passive"))
      (node (ref "R11") (pin "2") (pinfunction "2_2") (pintype "passive"))
      (node (ref "U1") (pin "P4") (pinfunction "EN_P4") (pintype "bidirectional"))
      (node (ref "U1") (pin "P5") (pinfunction "VIN_P5") (pintype "bidirectional"))
    )
    (net (code "46") (name "VCC_SENSE") (class "Default")
      (node (ref "R11") (pin "1") (pinfunction "1_1") (pintype "passive"))
      (node (ref "R12") (pin "2") (pinfunction "2_2") (pintype "passive"))
      (node (ref "U3") (pin "P6") (pinfunction "P1.5/TB0.2/UCACLK_P6") (pintype "bidirectional"))
    )
    (net (code "47") (name "VFILT") (class "Default")
      (node (ref "C39") (pin "2") (pinfunction "2_2") (pintype "passive"))
      (node (ref "R35") (pin "2") (pinfunction "2_2") (pintype "passive"))
      (node (ref "U3") (pin "P2") (pinfunction "P1.1/VREF+_P2") (pintype "bidirectional"))
      (node (ref "U7") (pin "P5") (pinfunction "IN+_P5") (pintype "bidirectional"))
    )
    (net (code "48") (name "VS+") (class "Default")
      (node (ref "C10") (pin "1") (pinfunction "1_1") (pintype "passive"))
      (node (ref "C4") (pin "1") (pinfunction "1_1") (pintype "passive"))
      (node (ref "C9") (pin "1") (pinfunction "1_1") (pintype "passive"))
      (node (ref "L1") (pin "1") (pinfunction "1_1") (pintype "passive"))
      (node (ref "R24") (pin "1") (pinfunction "1_1") (pintype "passive"))
      (node (ref "R7") (pin "2") (pinfunction "2_2") (pintype "passive"))
      (node (ref "U1") (pin "P2") (pinfunction "VOUT_P2") (pintype "bidirectional"))
    )
    (net (code "49") (name "VTEST") (class "Default")
      (node (ref "J2") (pin "PA.3") (pinfunction "P_PA.3") (pintype "bidirectional"))
      (node (ref "R3") (pin "1") (pinfunction "1_1") (pintype "passive"))
      (node (ref "RI1") (pin "1") (pinfunction "1_1") (pintype "passive"))
    )
    (net (code "50") (name "V_SENSE") (class "Default")
      (node (ref "RF") (pin "2") (pinfunction "2_2") (pintype "passive"))
      (node (ref "U3") (pin "P1") (pinfunction "P1.0/VREF-_P1") (pintype "bidirectional"))
      (node (ref "U6") (pin "P4") (pinfunction "OUT_P4") (pintype "bidirectional"))
    )
    (net (code "51") (name "ZC") (class "Default")
      (node (ref "D1") (pin "C") (pinfunction "C_C") (pintype "passive"))
      (node (ref "D2") (pin "A") (pinfunction "A_A") (pintype "passive"))
      (node (ref "R22") (pin "2") (pinfunction "2_2") (pintype "passive"))
      (node (ref "R3") (pin "2") (pinfunction "2_2") (pintype "passive"))
    )
    (net (code "52") (name "unconnected-(J1-4-PadP4)") (class "Default")
      (node (ref "J1") (pin "P4") (pinfunction "4_P4") (pintype "bidirectional"))
    )
    (net (code "53") (name "unconnected-(J1-6-PadP6)") (class "Default")
      (node (ref "J1") (pin "P6") (pinfunction "6_P6") (pintype "bidirectional"))
    )
    (net (code "54") (name "unconnected-(J4-SWO-Pad6)") (class "Default")
      (node (ref "J4") (pin "6") (pinfunction "SWO_6") (pintype "bidirectional"))
    )
    (net (code "55") (name "unconnected-(J4-~{RESET}-Pad3)") (class "Default")
      (node (ref "J4") (pin "3") (pinfunction "~{RESET}_3") (pintype "bidirectional"))
    )
    (net (code "56") (name "unconnected-(U3-P1.2{slash}TA1.1{slash}A2-PadP3)") (class "Default")
      (node (ref "U3") (pin "P3") (pinfunction "P1.2/TA1.1/A2_P3") (pintype "bidirectional"))
    )
    (net (code "57") (name "unconnected-(U3-P1.3{slash}TA1.2{slash}A3-PadP4)") (class "Default")
      (node (ref "U3") (pin "P4") (pinfunction "P1.3/TA1.2/A3_P4") (pintype "bidirectional"))
    )
    (net (code "58") (name "unconnected-(U4-P00{slash}AREF0-Pad4)") (class "Default")
      (node (ref "U4") (pin "4") (pinfunction "P00/AREF0_4") (pintype "bidirectional"))
    )
    (net (code "59") (name "unconnected-(U4-P01{slash}AIN2-Pad5)") (class "Default")
      (node (ref "U4") (pin "5") (pinfunction "P01/AIN2_5") (pintype "bidirectional"))
    )
    (net (code "60") (name "unconnected-(U4-P02{slash}AIN3-Pad6)") (class "Default")
      (node (ref "U4") (pin "6") (pinfunction "P02/AIN3_6") (pintype "bidirectional"))
    )
    (net (code "61") (name "unconnected-(U4-P03{slash}AIN4-Pad7)") (class "Default")
      (node (ref "U4") (pin "7") (pinfunction "P03/AIN4_7") (pintype "bidirectional"))
    )
    (net (code "62") (name "unconnected-(U4-P04{slash}AIN5-Pad8)") (class "Default")
      (node (ref "U4") (pin "8") (pinfunction "P04/AIN5_8") (pintype "bidirectional"))
    )
    (net (code "63") (name "unconnected-(U4-P06{slash}AIN7{slash}AREF1-Pad10)") (class "Default")
      (node (ref "U4") (pin "10") (pinfunction "P06/AIN7/AREF1_10") (pintype "bidirectional"))
    )
    (net (code "64") (name "unconnected-(U4-P07-Pad11)") (class "Default")
      (node (ref "U4") (pin "11") (pinfunction "P07_11") (pintype "bidirectional"))
    )
    (net (code "65") (name "unconnected-(U4-P08-Pad14)") (class "Default")
      (node (ref "U4") (pin "14") (pinfunction "P08_14") (pintype "bidirectional"))
    )
    (net (code "66") (name "unconnected-(U4-P09-Pad15)") (class "Default")
      (node (ref "U4") (pin "15") (pinfunction "P09_15") (pintype "bidirectional"))
    )
    (net (code "67") (name "unconnected-(U4-P10-Pad16)") (class "Default")
      (node (ref "U4") (pin "16") (pinfunction "P10_16") (pintype "bidirectional"))
    )
    (net (code "68") (name "unconnected-(U4-P11-Pad17)") (class "Default")
      (node (ref "U4") (pin "17") (pinfunction "P11_17") (pintype "bidirectional"))
    )
    (net (code "69") (name "unconnected-(U4-P12-Pad18)") (class "Default")
      (node (ref "U4") (pin "18") (pinfunction "P12_18") (pintype "bidirectional"))
    )
    (net (code "70") (name "unconnected-(U4-P13-Pad19)") (class "Default")
      (node (ref "U4") (pin "19") (pinfunction "P13_19") (pintype "bidirectional"))
    )
    (net (code "71") (name "unconnected-(U4-P14-Pad20)") (class "Default")
      (node (ref "U4") (pin "20") (pinfunction "P14_20") (pintype "bidirectional"))
    )
    (net (code "72") (name "unconnected-(U4-P15-Pad21)") (class "Default")
      (node (ref "U4") (pin "21") (pinfunction "P15_21") (pintype "bidirectional"))
    )
    (net (code "73") (name "unconnected-(U4-P16-Pad22)") (class "Default")
      (node (ref "U4") (pin "22") (pinfunction "P16_22") (pintype "bidirectional"))
    )
    (net (code "74") (name "unconnected-(U4-P17-Pad25)") (class "Default")
      (node (ref "U4") (pin "25") (pinfunction "P17_25") (pintype "bidirectional"))
    )
    (net (code "75") (name "unconnected-(U4-P18-Pad26)") (class "Default")
      (node (ref "U4") (pin "26") (pinfunction "P18_26") (pintype "bidirectional"))
    )
    (net (code "76") (name "unconnected-(U4-P19-Pad27)") (class "Default")
      (node (ref "U4") (pin "27") (pinfunction "P19_27") (pintype "bidirectional"))
    )
    (net (code "77") (name "unconnected-(U4-P20-Pad28)") (class "Default")
      (node (ref "U4") (pin "28") (pinfunction "P20_28") (pintype "bidirectional"))
    )
    (net (code "78") (name "unconnected-(U4-P21-Pad40)") (class "Default")
      (node (ref "U4") (pin "40") (pinfunction "P21_40") (pintype "bidirectional"))
    )
    (net (code "79") (name "unconnected-(U4-P22-Pad41)") (class "Default")
      (node (ref "U4") (pin "41") (pinfunction "P22_41") (pintype "bidirectional"))
    )
    (net (code "80") (name "unconnected-(U4-P23-Pad42)") (class "Default")
      (node (ref "U4") (pin "42") (pinfunction "P23_42") (pintype "bidirectional"))
    )
    (net (code "81") (name "unconnected-(U4-P24-Pad43)") (class "Default")
      (node (ref "U4") (pin "43") (pinfunction "P24_43") (pintype "bidirectional"))
    )
    (net (code "82") (name "unconnected-(U4-P25-Pad44)") (class "Default")
      (node (ref "U4") (pin "44") (pinfunction "P25_44") (pintype "bidirectional"))
    )
    (net (code "83") (name "unconnected-(U4-P26{slash}AIN0{slash}XL2-Pad45)") (class "Default")
      (node (ref "U4") (pin "45") (pinfunction "P26/AIN0/XL2_45") (pintype "bidirectional"))
    )
    (net (code "84") (name "unconnected-(U4-P30-Pad3)") (class "Default")
      (node (ref "U4") (pin "3") (pinfunction "P30_3") (pintype "bidirectional"))
    )
  )
)
